# SD.net
KiCad netlist of a schematic drawn in Altium Designer
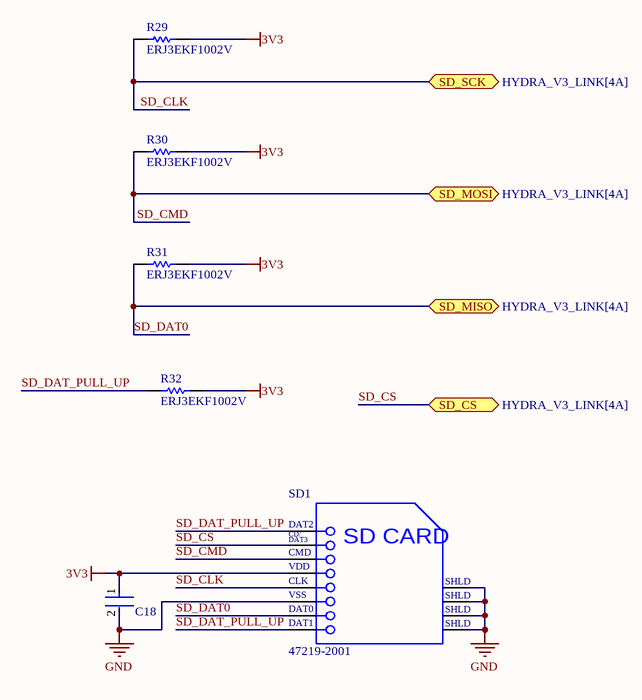
[diagram p0: SD.SchDoc]

(export (version "E")
  (design (tool "Eeschema 10.0.6"))
  (components
    (comp (ref "C18")
      (value "C0402C104K8PACTU")
      (footprint "FP-C0402-BB-MFG")
      (description "CAP CER 0.1UF 10V X5R 0402")
      (fields (field (name "MANUFACTURER") "Kemet") (field (name "TOLERANCE") "0.1"))
      (libsource (lib "Altium Content Vault") (part "b4654b650e69147ec39a6b967a45e02"))
    )
    (comp (ref "R29")
      (value "ERJ3EKF1002V")
      (footprint "RESC1609X55X30LL15T15")
      (description "Chip Resistor, 10 KOhm, +/- 1%, 0.1 W, -55 to 155 degC, 0603 (1608 Metric), RoHS, Tape and Reel")
      (fields (field (name "TOLERANCE") "1%") (field (name "MANUFACTURER") "Panasonic"))
      (libsource (lib "Altium Content Vault") (part "RES-2"))
    )
    (comp (ref "R30")
      (value "ERJ3EKF1002V")
      (footprint "RESC1609X55X30LL15T15")
      (description "Chip Resistor, 10 KOhm, +/- 1%, 0.1 W, -55 to 155 degC, 0603 (1608 Metric), RoHS, Tape and Reel")
      (fields (field (name "TOLERANCE") "1%") (field (name "MANUFACTURER") "Panasonic"))
      (libsource (lib "Altium Content Vault") (part "RES-2"))
    )
    (comp (ref "R31")
      (value "ERJ3EKF1002V")
      (footprint "RESC1609X55X30LL15T15")
      (description "Chip Resistor, 10 KOhm, +/- 1%, 0.1 W, -55 to 155 degC, 0603 (1608 Metric), RoHS, Tape and Reel")
      (fields (field (name "TOLERANCE") "1%") (field (name "MANUFACTURER") "Panasonic"))
      (libsource (lib "Altium Content Vault") (part "RES-2"))
    )
    (comp (ref "R32")
      (value "ERJ3EKF1002V")
      (footprint "RESC1609X55X30LL15T15")
      (description "Chip Resistor, 10 KOhm, +/- 1%, 0.1 W, -55 to 155 degC, 0603 (1608 Metric), RoHS, Tape and Reel")
      (fields (field (name "TOLERANCE") "1%") (field (name "MANUFACTURER") "Panasonic"))
      (libsource (lib "Altium Content Vault") (part "RES-2"))
    )
    (comp (ref "SD1")
      (value "47219-2001")
      (footprint "MOLX-47219-2001-8_V")
      (description "MicroSD Card Connector, Hinge Type, -40 to 85 degC, 8-Pin SMD, RoHS, Tape and Reel")
      (fields (field (name "MANUFACTURER") "Molex"))
      (libsource (lib "Altium Content Vault") (part "CN-SD-8-4S"))
    )
  )
  (nets
    (net (code "1") (name "/SD_CLK") (class "Default")
      (node (ref "R29") (pin "1") (pinfunction "1_1") (pintype "passive"))
      (node (ref "SD1") (pin "5") (pinfunction "CLK_5") (pintype "passive"))
    )
    (net (code "2") (name "/SD_CMD") (class "Default")
      (node (ref "R30") (pin "1") (pinfunction "1_1") (pintype "passive"))
      (node (ref "SD1") (pin "3") (pinfunction "CMD_3") (pintype "passive"))
    )
    (net (code "3") (name "/SD_CS") (class "Default")
      (node (ref "SD1") (pin "2") (pinfunction "CD/DAT3_2") (pintype "passive"))
    )
    (net (code "4") (name "/SD_DAT0") (class "Default")
      (node (ref "R31") (pin "1") (pinfunction "1_1") (pintype "passive"))
      (node (ref "SD1") (pin "7") (pinfunction "DAT0_7") (pintype "passive"))
    )
    (net (code "5") (name "/SD_DAT_PULL_UP") (class "Default")
      (node (ref "R32") (pin "1") (pinfunction "1_1") (pintype "passive"))
      (node (ref "SD1") (pin "1") (pinfunction "DAT2_1") (pintype "passive"))
      (node (ref "SD1") (pin "8") (pinfunction "DAT1_8") (pintype "passive"))
    )
    (net (code "6") (name "3V3") (class "Default")
      (node (ref "C18") (pin "1") (pinfunction "1_1") (pintype "passive"))
      (node (ref "R29") (pin "2") (pinfunction "2_2") (pintype "passive"))
      (node (ref "R30") (pin "2") (pinfunction "2_2") (pintype "passive"))
      (node (ref "R31") (pin "2") (pinfunction "2_2") (pintype "passive"))
      (node (ref "R32") (pin "2") (pinfunction "2_2") (pintype "passive"))
      (node (ref "SD1") (pin "4") (pinfunction "VDD_4") (pintype "passive"))
    )
    (net (code "7") (name "GND") (class "Default")
      (node (ref "C18") (pin "2") (pinfunction "2_2") (pintype "passive"))
      (node (ref "SD1") (pin "10") (pinfunction "SHLD_10") (pintype "passive"))
      (node (ref "SD1") (pin "11") (pinfunction "SHLD_11") (pintype "passive"))
      (node (ref "SD1") (pin "12") (pinfunction "SHLD_12") (pintype "passive"))
      (node (ref "SD1") (pin "6") (pinfunction "VSS_6") (pintype "passive"))
      (node (ref "SD1") (pin "9") (pinfunction "SHLD_9") (pintype "passive"))
    )
  )
)
